# BLEbee-1_0_0-REV-B.net
KiCad netlist of a schematic drawn in EAGLE
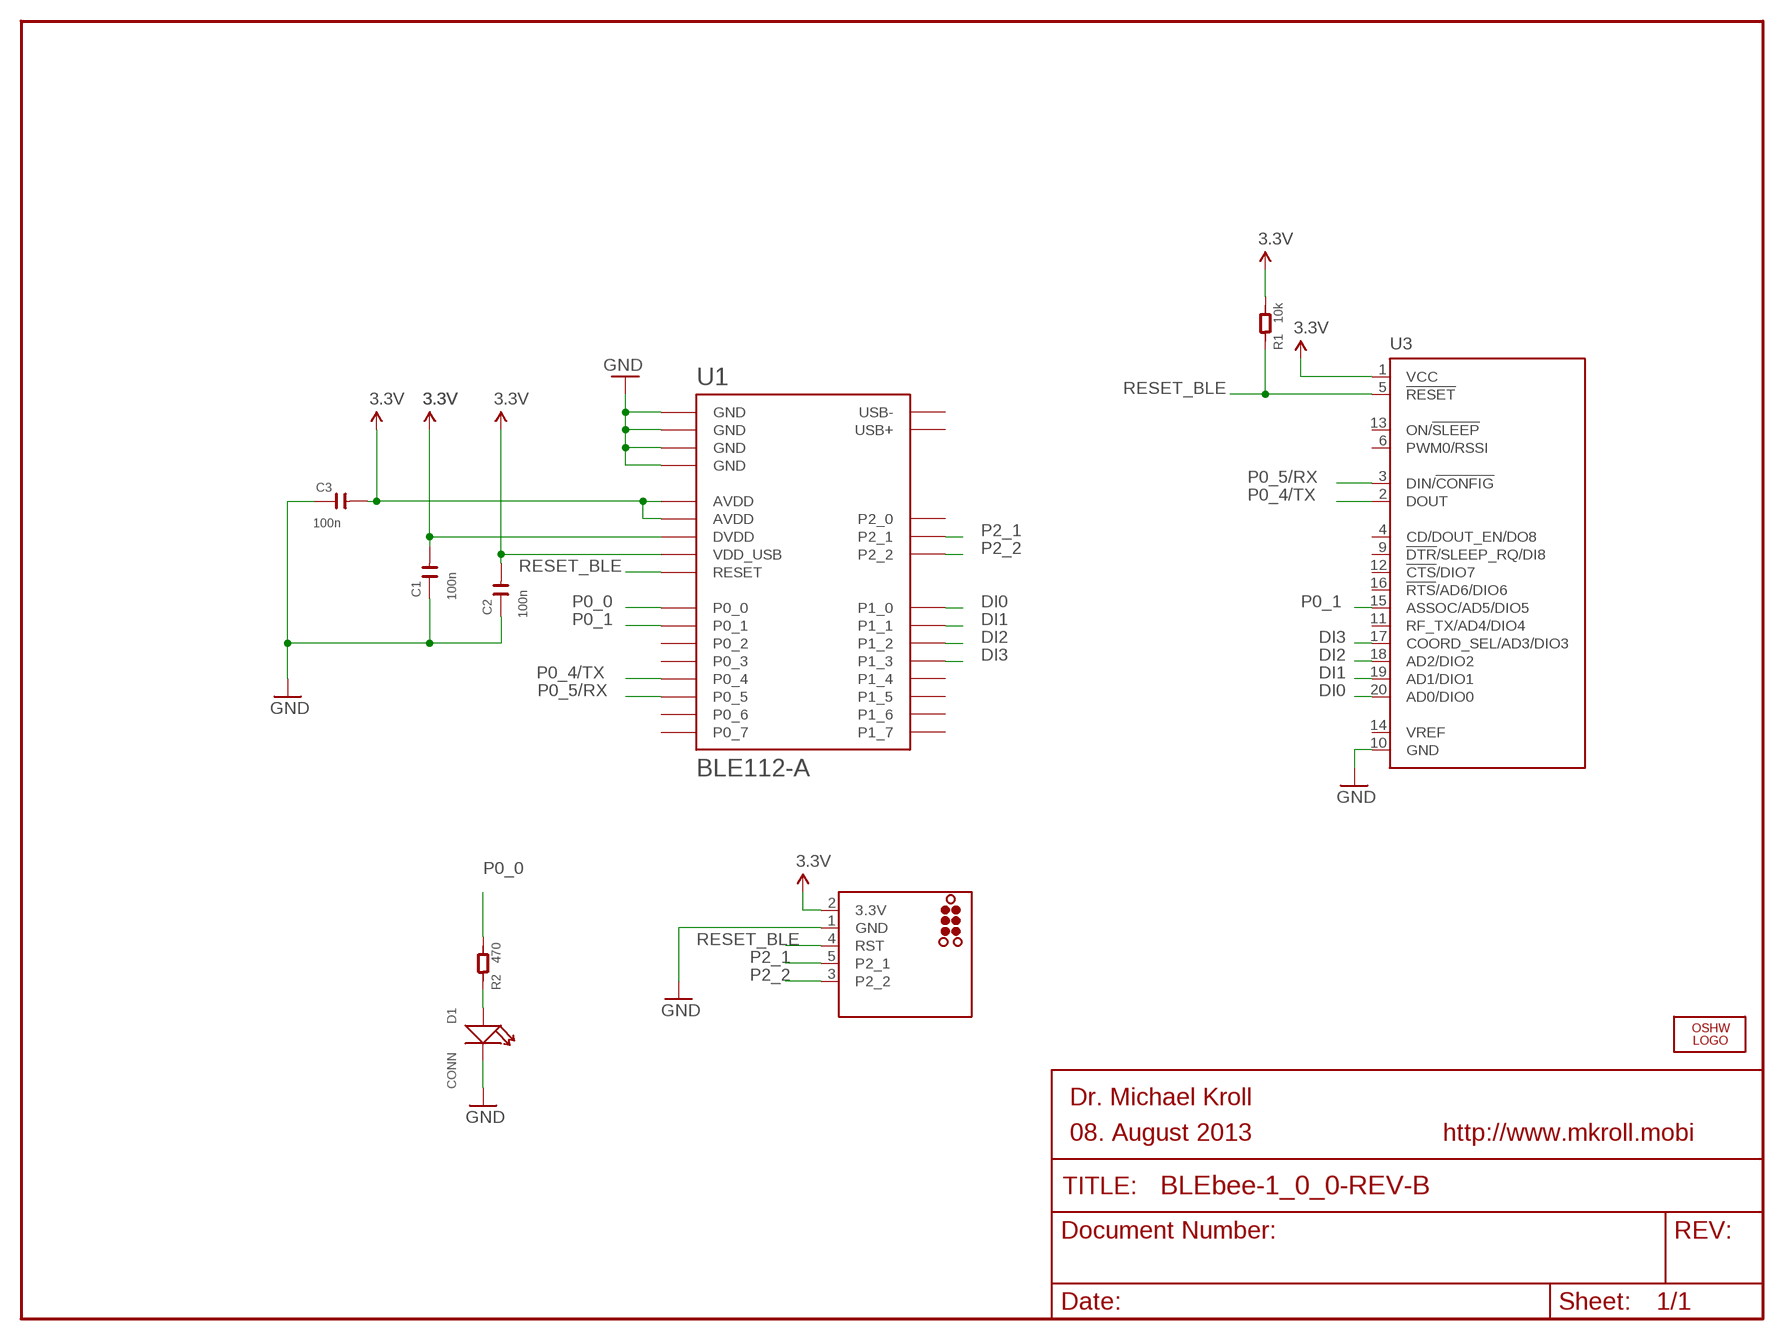
[diagram p0: schematic, sheet 1]

(export (version "E")
  (design (tool "Eeschema 10.0.6"))
  (components
    (comp (ref "C1")
      (value "100n")
      (footprint "eagle-import:C0603")
      (libsource (lib "eagle-import") (part "C-0603"))
    )
    (comp (ref "C2")
      (value "100n")
      (footprint "eagle-import:C0603")
      (libsource (lib "eagle-import") (part "C-0603"))
    )
    (comp (ref "C3")
      (value "100n")
      (footprint "eagle-import:C0603")
      (libsource (lib "eagle-import") (part "C-0603"))
    )
    (comp (ref "D1")
      (value "CONN")
      (footprint "eagle-import:LED0603")
      (libsource (lib "eagle-import") (part "LED"))
    )
    (comp (ref "J1")
      (value "TC2030-CC-DEBUGGER")
      (footprint "eagle-import:TC2030-MCP-NL")
      (libsource (lib "eagle-import") (part "TC2030-CC-DEBUGGER"))
    )
    (comp (ref "LOGO1")
      (value "LOGO-OSHW-6MILX0100-NT")
      (footprint "eagle-import:OSHW_6X100_NOTEXT")
      (libsource (lib "eagle-import") (part "LOGO-OSHW-6MILX0100-NT"))
    )
    (comp (ref "R1")
      (value "10k")
      (footprint "eagle-import:R0603")
      (libsource (lib "eagle-import") (part "R-0603"))
    )
    (comp (ref "R2")
      (value "470")
      (footprint "eagle-import:R0603")
      (libsource (lib "eagle-import") (part "R-0603"))
    )
    (comp (ref "U1")
      (value "BLE112-A")
      (footprint "eagle-import:BLE112-A")
      (libsource (lib "eagle-import") (part "BLE112-A"))
    )
    (comp (ref "U3")
      (value "MODULE_BEE-XBEE-DIP")
      (footprint "eagle-import:MODULE_20P-DIP-2.0-W_-SILK")
      (libsource (lib "eagle-import") (part "MODULE_BEE-XBEE-DIP"))
    )
  )
  (nets
    (net (code "1") (name "/DI0") (class "Default")
      (node (ref "U1") (pin "P1_0") (pinfunction "P1_0_P1_0") (pintype "bidirectional"))
      (node (ref "U3") (pin "20") (pinfunction "AD0/DIO0_20") (pintype "bidirectional"))
    )
    (net (code "2") (name "/DI1") (class "Default")
      (node (ref "U1") (pin "P1_1") (pinfunction "P1_1_P1_1") (pintype "bidirectional"))
      (node (ref "U3") (pin "19") (pinfunction "AD1/DIO1_19") (pintype "bidirectional"))
    )
    (net (code "3") (name "/DI2") (class "Default")
      (node (ref "U1") (pin "P1_2") (pinfunction "P1_2_P1_2") (pintype "bidirectional"))
      (node (ref "U3") (pin "18") (pinfunction "AD2/DIO2_18") (pintype "bidirectional"))
    )
    (net (code "4") (name "/DI3") (class "Default")
      (node (ref "U1") (pin "P1_3") (pinfunction "P1_3_P1_3") (pintype "bidirectional"))
      (node (ref "U3") (pin "17") (pinfunction "COORD_SEL/AD3/DIO3_17") (pintype "bidirectional"))
    )
    (net (code "5") (name "/P0_0") (class "Default")
      (node (ref "R2") (pin "2") (pinfunction "2_2") (pintype "bidirectional"))
      (node (ref "U1") (pin "P0_0") (pinfunction "P0_0_P0_0") (pintype "bidirectional"))
    )
    (net (code "6") (name "/P0_1") (class "Default")
      (node (ref "U1") (pin "P0_1") (pinfunction "P0_1_P0_1") (pintype "bidirectional"))
      (node (ref "U3") (pin "15") (pinfunction "ASSOC/AD5/DIO5_15") (pintype "bidirectional"))
    )
    (net (code "7") (name "/P0_4{slash}TX") (class "Default")
      (node (ref "U1") (pin "P0_4") (pinfunction "P0_4_P0_4") (pintype "bidirectional"))
      (node (ref "U3") (pin "2") (pinfunction "DOUT_2") (pintype "output"))
    )
    (net (code "8") (name "/P0_5{slash}RX") (class "Default")
      (node (ref "U1") (pin "P0_5") (pinfunction "P0_5_P0_5") (pintype "bidirectional"))
      (node (ref "U3") (pin "3") (pinfunction "DIN/~{CONFIG}_3") (pintype "input"))
    )
    (net (code "9") (name "/P2_1") (class "Default")
      (node (ref "J1") (pin "5") (pinfunction "P2_1_5") (pintype "bidirectional"))
      (node (ref "U1") (pin "P2_1") (pinfunction "P2_1_P2_1") (pintype "bidirectional"))
    )
    (net (code "10") (name "/P2_2") (class "Default")
      (node (ref "J1") (pin "3") (pinfunction "P2_2_3") (pintype "bidirectional"))
      (node (ref "U1") (pin "P2_2") (pinfunction "P2_2_P2_2") (pintype "bidirectional"))
    )
    (net (code "11") (name "/RESET_BLE") (class "Default")
      (node (ref "J1") (pin "4") (pinfunction "RST_4") (pintype "bidirectional"))
      (node (ref "R1") (pin "1") (pinfunction "1_1") (pintype "bidirectional"))
      (node (ref "U1") (pin "RESET") (pinfunction "RESET_RESET") (pintype "input"))
      (node (ref "U3") (pin "5") (pinfunction "~{RESET}_5") (pintype "input"))
    )
    (net (code "12") (name "3.3V") (class "Default")
      (node (ref "C1") (pin "1") (pinfunction "1_1") (pintype "bidirectional"))
      (node (ref "C2") (pin "1") (pinfunction "1_1") (pintype "bidirectional"))
      (node (ref "C3") (pin "1") (pinfunction "1_1") (pintype "bidirectional"))
      (node (ref "J1") (pin "2") (pinfunction "3.3V_2") (pintype "power_in"))
      (node (ref "R1") (pin "2") (pinfunction "2_2") (pintype "bidirectional"))
      (node (ref "U1") (pin "AVDD1") (pinfunction "AVDD_AVDD1") (pintype "power_in"))
      (node (ref "U1") (pin "AVDD2") (pinfunction "AVDD_AVDD2") (pintype "power_in"))
      (node (ref "U1") (pin "DVDD") (pinfunction "DVDD_DVDD") (pintype "power_in"))
      (node (ref "U1") (pin "VDD_USB") (pinfunction "VDD_USB_VDD_USB") (pintype "power_in"))
      (node (ref "U3") (pin "1") (pinfunction "VCC_1") (pintype "power_in"))
    )
    (net (code "13") (name "GND") (class "Default")
      (node (ref "C1") (pin "2") (pinfunction "2_2") (pintype "bidirectional"))
      (node (ref "C2") (pin "2") (pinfunction "2_2") (pintype "bidirectional"))
      (node (ref "C3") (pin "2") (pinfunction "2_2") (pintype "bidirectional"))
      (node (ref "D1") (pin "-") (pinfunction "-_-") (pintype "passive"))
      (node (ref "J1") (pin "1") (pinfunction "GND_1") (pintype "power_in"))
      (node (ref "U1") (pin "GND1") (pinfunction "GND_GND1") (pintype "power_in"))
      (node (ref "U1") (pin "GND2") (pinfunction "GND_GND2") (pintype "power_in"))
      (node (ref "U1") (pin "GND3") (pinfunction "GND_GND3") (pintype "power_in"))
      (node (ref "U1") (pin "GND4") (pinfunction "GND_GND4") (pintype "power_in"))
      (node (ref "U3") (pin "10") (pinfunction "GND_10") (pintype "bidirectional"))
    )
    (net (code "14") (name "Net-(D1-Pad+)") (class "Default")
      (node (ref "D1") (pin "+") (pinfunction "+_+") (pintype "passive"))
      (node (ref "R2") (pin "1") (pinfunction "1_1") (pintype "bidirectional"))
    )
    (net (code "15") (name "unconnected-(U1-PadP0_2)") (class "Default")
      (node (ref "U1") (pin "P0_2") (pinfunction "P0_2_P0_2") (pintype "bidirectional"))
    )
    (net (code "16") (name "unconnected-(U1-PadP0_3)") (class "Default")
      (node (ref "U1") (pin "P0_3") (pinfunction "P0_3_P0_3") (pintype "bidirectional"))
    )
    (net (code "17") (name "unconnected-(U1-PadP0_6)") (class "Default")
      (node (ref "U1") (pin "P0_6") (pinfunction "P0_6_P0_6") (pintype "bidirectional"))
    )
    (net (code "18") (name "unconnected-(U1-PadP0_7)") (class "Default")
      (node (ref "U1") (pin "P0_7") (pinfunction "P0_7_P0_7") (pintype "bidirectional"))
    )
    (net (code "19") (name "unconnected-(U1-PadP1_4)") (class "Default")
      (node (ref "U1") (pin "P1_4") (pinfunction "P1_4_P1_4") (pintype "bidirectional"))
    )
    (net (code "20") (name "unconnected-(U1-PadP1_5)") (class "Default")
      (node (ref "U1") (pin "P1_5") (pinfunction "P1_5_P1_5") (pintype "bidirectional"))
    )
    (net (code "21") (name "unconnected-(U1-PadP1_6)") (class "Default")
      (node (ref "U1") (pin "P1_6") (pinfunction "P1_6_P1_6") (pintype "bidirectional"))
    )
    (net (code "22") (name "unconnected-(U1-PadP1_7)") (class "Default")
      (node (ref "U1") (pin "P1_7") (pinfunction "P1_7_P1_7") (pintype "bidirectional"))
    )
    (net (code "23") (name "unconnected-(U1-PadP2_0)") (class "Default")
      (node (ref "U1") (pin "P2_0") (pinfunction "P2_0_P2_0") (pintype "bidirectional"))
    )
    (net (code "24") (name "unconnected-(U1-PadUSB+)") (class "Default")
      (node (ref "U1") (pin "USB+") (pinfunction "USB+_USB+") (pintype "bidirectional"))
    )
    (net (code "25") (name "unconnected-(U1-PadUSB-)") (class "Default")
      (node (ref "U1") (pin "USB-") (pinfunction "USB-_USB-") (pintype "bidirectional"))
    )
    (net (code "26") (name "unconnected-(U3-CD{slash}DOUT_EN{slash}DO8-Pad4)") (class "Default")
      (node (ref "U3") (pin "4") (pinfunction "CD/DOUT_EN/DO8_4") (pintype "output"))
    )
    (net (code "27") (name "unconnected-(U3-ON{slash}~{SLEEP}-Pad13)") (class "Default")
      (node (ref "U3") (pin "13") (pinfunction "ON/~{SLEEP}_13") (pintype "output"))
    )
    (net (code "28") (name "unconnected-(U3-PWM0{slash}RSSI-Pad6)") (class "Default")
      (node (ref "U3") (pin "6") (pinfunction "PWM0/RSSI_6") (pintype "output"))
    )
    (net (code "29") (name "unconnected-(U3-RF_TX{slash}AD4{slash}DIO4-Pad11)") (class "Default")
      (node (ref "U3") (pin "11") (pinfunction "RF_TX/AD4/DIO4_11") (pintype "bidirectional"))
    )
    (net (code "30") (name "unconnected-(U3-VREF-Pad14)") (class "Default")
      (node (ref "U3") (pin "14") (pinfunction "VREF_14") (pintype "input"))
    )
    (net (code "31") (name "unconnected-(U3-~{CTS}{slash}DIO7-Pad12)") (class "Default")
      (node (ref "U3") (pin "12") (pinfunction "~{CTS}/DIO7_12") (pintype "bidirectional"))
    )
    (net (code "32") (name "unconnected-(U3-~{DTR}{slash}SLEEP_RQ{slash}DI8-Pad9)") (class "Default")
      (node (ref "U3") (pin "9") (pinfunction "~{DTR}/SLEEP_RQ/DI8_9") (pintype "bidirectional"))
    )
    (net (code "33") (name "unconnected-(U3-~{RTS}{slash}AD6{slash}DIO6-Pad16)") (class "Default")
      (node (ref "U3") (pin "16") (pinfunction "~{RTS}/AD6/DIO6_16") (pintype "bidirectional"))
    )
  )
)
